# Power_Inputs.net
KiCad netlist of a schematic drawn in Altium Designer
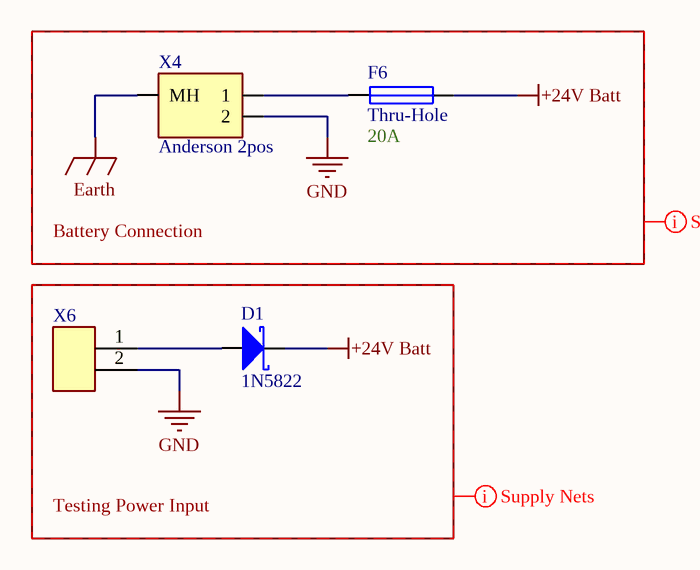
[diagram p0: Power Inputs.SchDoc]

(export (version "E")
  (design (tool "Eeschema 10.0.6"))
  (components
    (comp (ref "D1")
      (value "1N5822")
      (footprint "[Diode] Thru-Hole Schottky")
      (fields (field (name "MOUSER PART #") "511-1N5822"))
      (libsource (lib "RADM Components") (part "[Diode] Thru-Hole Schottky"))
    )
    (comp (ref "F6")
      (value "Thru-Hole")
      (footprint "[Fuse] Thru-Hole Blade")
      (fields (field (name "CAPACITY") "20A"))
      (libsource (lib "RADM Components") (part "[Fuse] Thru-Hole Blade"))
    )
    (comp (ref "X4")
      (value "Anderson 2pos")
      (footprint "[Anderson] 2pos Right-Angle 1327G17")
      (libsource (lib "RADM Connectors") (part "[Anderson] 2pos Right-Angle 1327G17"))
    )
    (comp (ref "X6")
      (value "2pin Screw Terminal")
      (footprint "[Screw Terminal] 2pin 5mm")
      (libsource (lib "RADM Connectors") (part "[Screw Terminal] 2pin"))
    )
  )
  (nets
    (net (code "1") (name "+24V Batt") (class "Default")
      (node (ref "D1") (pin "1") (pinfunction "K_1") (pintype "passive"))
      (node (ref "F6") (pin "2") (pinfunction "2_2") (pintype "passive"))
    )
    (net (code "2") (name "Earth") (class "Default")
      (node (ref "X4") (pin "MH") (pinfunction "MH_MH") (pintype "power_in"))
    )
    (net (code "3") (name "GND") (class "Default")
      (node (ref "X4") (pin "2") (pinfunction "2_2") (pintype "passive"))
      (node (ref "X6") (pin "2") (pintype "power_in"))
    )
    (net (code "4") (name "Net-(D1-A)") (class "Default")
      (node (ref "D1") (pin "2") (pinfunction "A_2") (pintype "passive"))
      (node (ref "X6") (pin "1") (pintype "power_in"))
    )
    (net (code "5") (name "Net-(F6-Pad1)") (class "Default")
      (node (ref "F6") (pin "1") (pinfunction "1_1") (pintype "passive"))
      (node (ref "X4") (pin "1") (pinfunction "1_1") (pintype "passive"))
    )
  )
)
